# MCU_et_al.net
KiCad netlist of a schematic drawn in Altium Designer
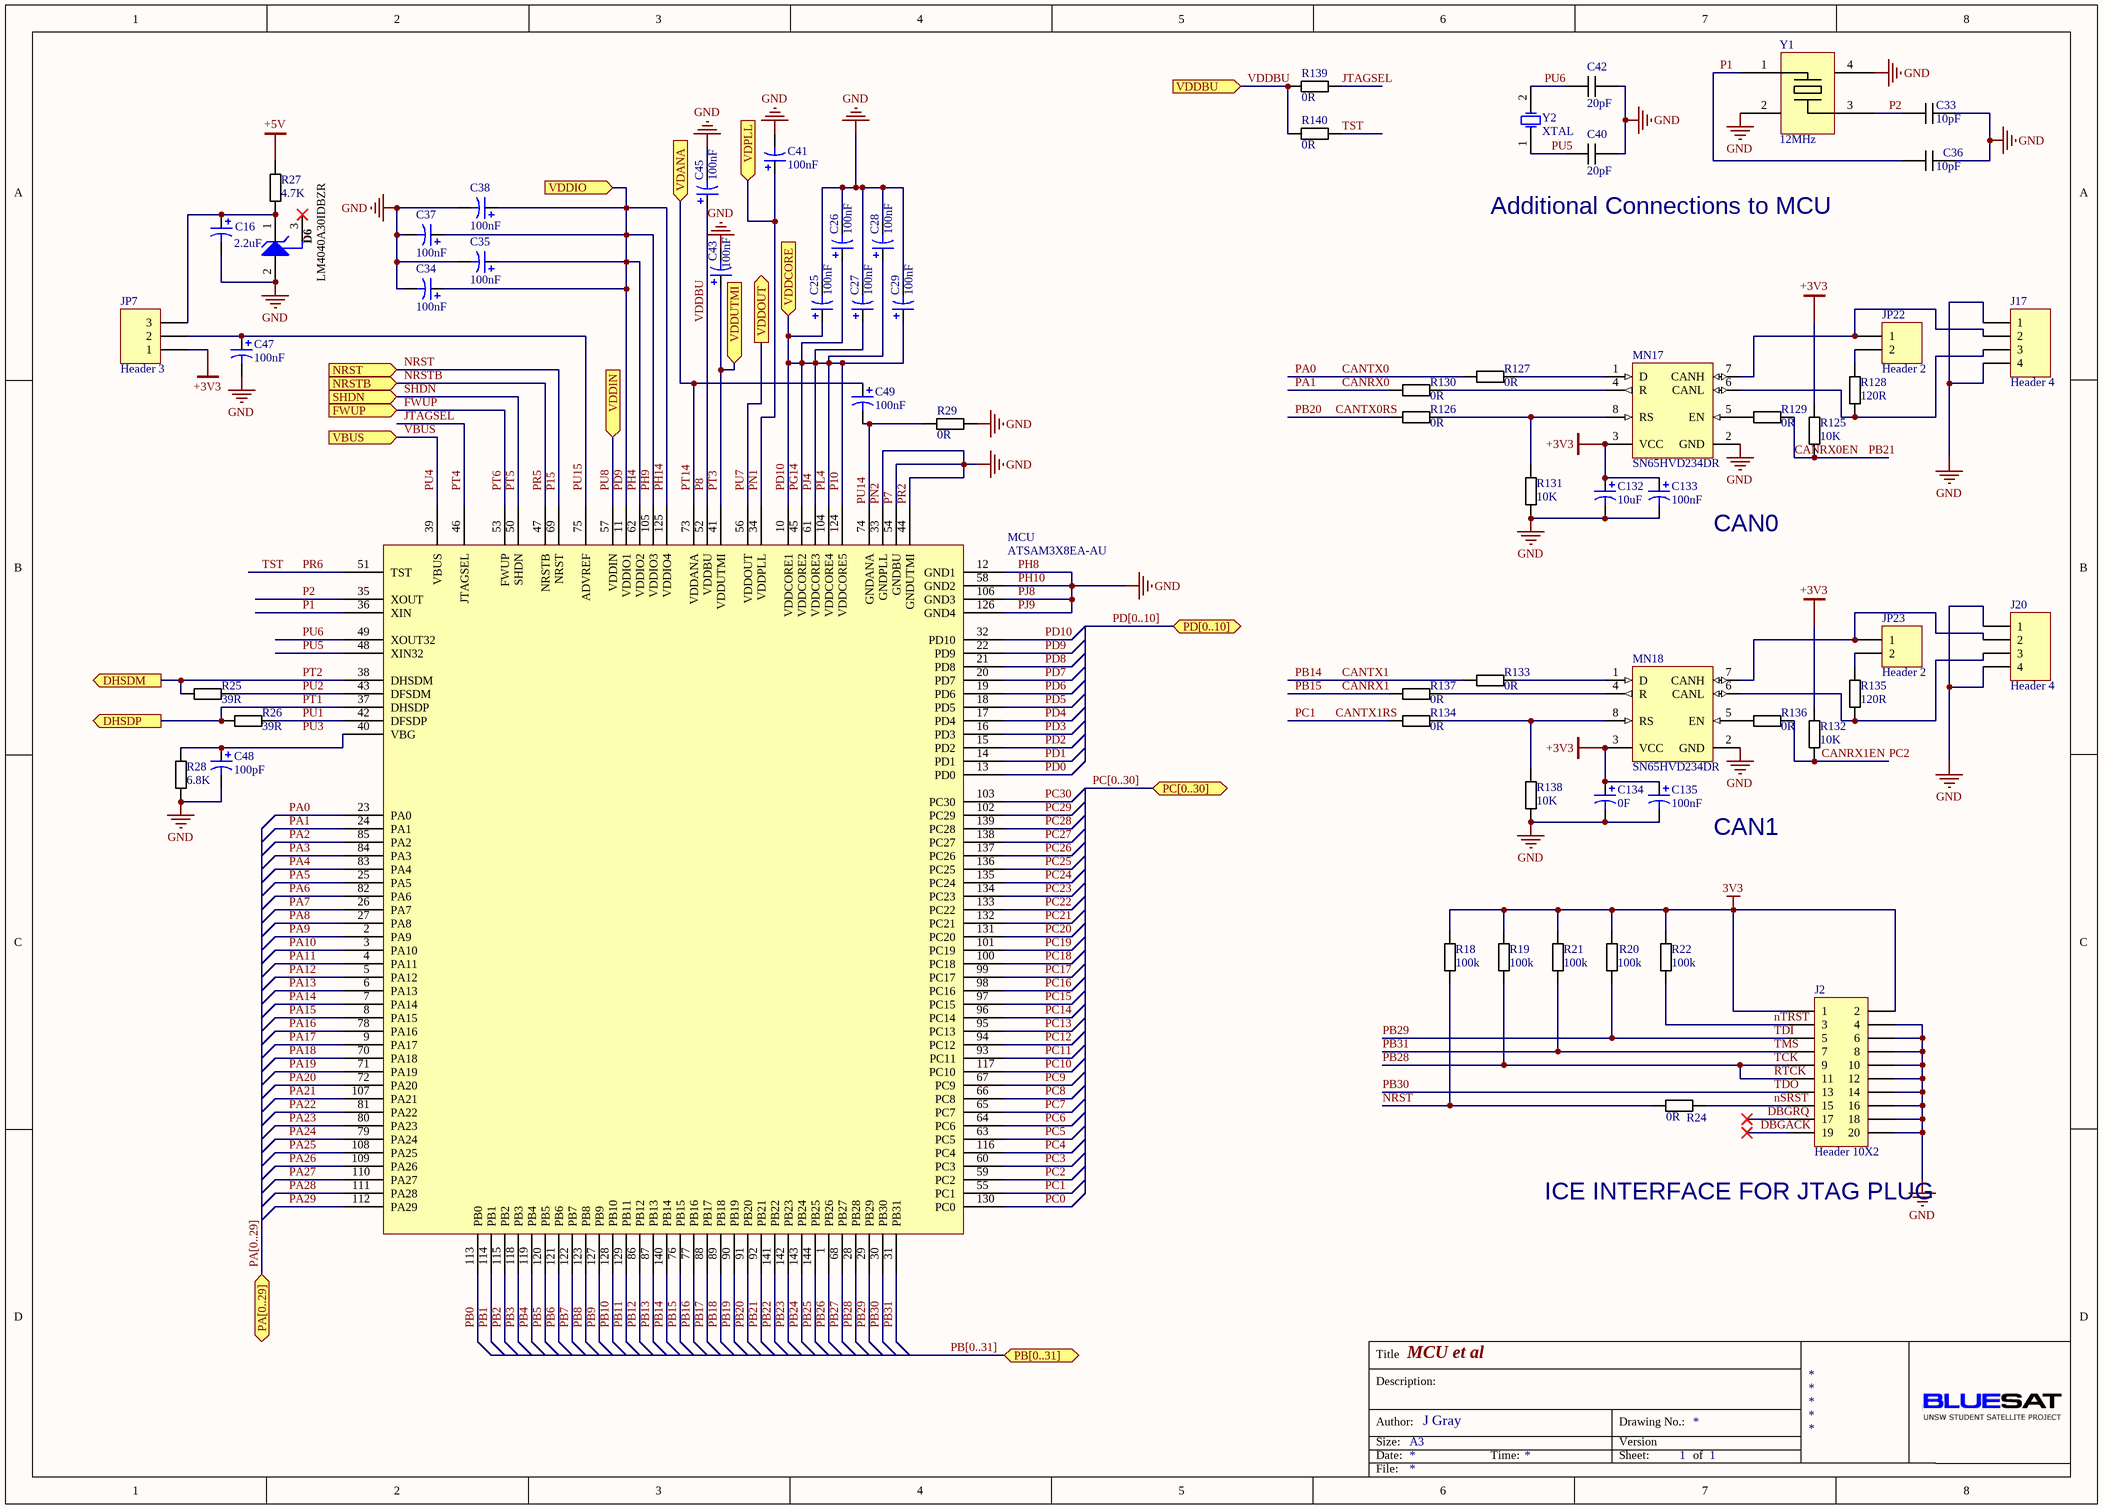
[diagram p0: MCU et al.SchDoc]

(export (version "E")
  (design (tool "Eeschema 10.0.6"))
  (components
    (comp (ref "C16")
      (value "2.2uF")
      (footprint "0805 Cap")
      (description "Polarized Capacitor (Surface Mount)")
      (fields (field (name "Comment") "Cap Pol3") (field (name "PUBLISHER") "Altium Limited"))
      (libsource (lib "Miscellaneous Devices") (part "Cap Pol3"))
    )
    (comp (ref "C25")
      (value "100nF")
      (footprint "0805 Cap")
      (description "Polarized Capacitor (Surface Mount)")
      (fields (field (name "Comment") "Cap Pol3") (field (name "PUBLISHER") "Altium Limited"))
      (libsource (lib "Miscellaneous Devices") (part "Cap Pol3"))
    )
    (comp (ref "C26")
      (value "100nF")
      (footprint "0805 Cap")
      (description "Polarized Capacitor (Surface Mount)")
      (fields (field (name "Comment") "Cap Pol3") (field (name "PUBLISHER") "Altium Limited"))
      (libsource (lib "Miscellaneous Devices") (part "Cap Pol3"))
    )
    (comp (ref "C27")
      (value "100nF")
      (footprint "0805 Cap")
      (description "Polarized Capacitor (Surface Mount)")
      (fields (field (name "Comment") "Cap Pol3") (field (name "PUBLISHER") "Altium Limited"))
      (libsource (lib "Miscellaneous Devices") (part "Cap Pol3"))
    )
    (comp (ref "C28")
      (value "100nF")
      (footprint "0805 Cap")
      (description "Polarized Capacitor (Surface Mount)")
      (fields (field (name "Comment") "Cap Pol3") (field (name "PUBLISHER") "Altium Limited"))
      (libsource (lib "Miscellaneous Devices") (part "Cap Pol3"))
    )
    (comp (ref "C29")
      (value "100nF")
      (footprint "0805 Cap")
      (description "Polarized Capacitor (Surface Mount)")
      (fields (field (name "Comment") "Cap Pol3") (field (name "PUBLISHER") "Altium Limited"))
      (libsource (lib "Miscellaneous Devices") (part "Cap Pol3"))
    )
    (comp (ref "C33")
      (value "10pF")
      (footprint "0805 Cap")
      (description "0805 MLCC - X7R, 10%")
      (fields (field (name "Comment") "0805 Cap"))
      (libsource (lib "Schlib1") (part "0805 MLCC - X7R, 10%"))
    )
    (comp (ref "C34")
      (value "100nF")
      (footprint "0805 Cap")
      (description "Polarized Capacitor (Surface Mount)")
      (fields (field (name "Comment") "Cap Pol3") (field (name "PUBLISHER") "Altium Limited"))
      (libsource (lib "Miscellaneous Devices") (part "Cap Pol3"))
    )
    (comp (ref "C35")
      (value "100nF")
      (footprint "0805 Cap")
      (description "Polarized Capacitor (Surface Mount)")
      (fields (field (name "Comment") "Cap Pol3") (field (name "PUBLISHER") "Altium Limited"))
      (libsource (lib "Miscellaneous Devices") (part "Cap Pol3"))
    )
    (comp (ref "C36")
      (value "10pF")
      (footprint "0805 Cap")
      (description "0805 MLCC - X7R, 10%")
      (fields (field (name "Comment") "0805 Cap"))
      (libsource (lib "Schlib1") (part "0805 MLCC - X7R, 10%"))
    )
    (comp (ref "C37")
      (value "100nF")
      (footprint "0805 Cap")
      (description "Polarized Capacitor (Surface Mount)")
      (fields (field (name "Comment") "Cap Pol3") (field (name "PUBLISHER") "Altium Limited"))
      (libsource (lib "Miscellaneous Devices") (part "Cap Pol3"))
    )
    (comp (ref "C38")
      (value "100nF")
      (footprint "0805 Cap")
      (description "Polarized Capacitor (Surface Mount)")
      (fields (field (name "Comment") "Cap Pol3") (field (name "PUBLISHER") "Altium Limited"))
      (libsource (lib "Miscellaneous Devices") (part "Cap Pol3"))
    )
    (comp (ref "C40")
      (value "20pF")
      (footprint "0805 Cap")
      (description "0805 MLCC - X7R, 10%")
      (fields (field (name "Comment") "0805 Cap"))
      (libsource (lib "Schlib1") (part "0805 MLCC - X7R, 10%"))
    )
    (comp (ref "C41")
      (value "100nF")
      (footprint "0805 Cap")
      (description "Polarized Capacitor (Surface Mount)")
      (fields (field (name "Comment") "Cap Pol3") (field (name "PUBLISHER") "Altium Limited"))
      (libsource (lib "Miscellaneous Devices") (part "Cap Pol3"))
    )
    (comp (ref "C42")
      (value "20pF")
      (footprint "0805 Cap")
      (description "0805 MLCC - X7R, 10%")
      (fields (field (name "Comment") "0805 Cap"))
      (libsource (lib "Schlib1") (part "0805 MLCC - X7R, 10%"))
    )
    (comp (ref "C43")
      (value "100nF")
      (footprint "0805 Cap")
      (description "Polarized Capacitor (Surface Mount)")
      (fields (field (name "Comment") "Cap Pol3") (field (name "PUBLISHER") "Altium Limited"))
      (libsource (lib "Miscellaneous Devices") (part "Cap Pol3"))
    )
    (comp (ref "C45")
      (value "100nF")
      (footprint "0805 Cap")
      (description "Polarized Capacitor (Surface Mount)")
      (fields (field (name "Comment") "Cap Pol3") (field (name "PUBLISHER") "Altium Limited"))
      (libsource (lib "Miscellaneous Devices") (part "Cap Pol3"))
    )
    (comp (ref "C47")
      (value "100nF")
      (footprint "0805 Cap")
      (description "Polarized Capacitor (Surface Mount)")
      (fields (field (name "Comment") "Cap Pol3") (field (name "PUBLISHER") "Altium Limited"))
      (libsource (lib "Miscellaneous Devices") (part "Cap Pol3"))
    )
    (comp (ref "C48")
      (value "100pF")
      (footprint "0805 Cap")
      (description "Polarized Capacitor (Surface Mount)")
      (fields (field (name "Comment") "Cap Pol3") (field (name "PUBLISHER") "Altium Limited"))
      (libsource (lib "Miscellaneous Devices") (part "Cap Pol3"))
    )
    (comp (ref "C49")
      (value "100nF")
      (footprint "0805 Cap")
      (description "Polarized Capacitor (Surface Mount)")
      (fields (field (name "Comment") "Cap Pol3") (field (name "PUBLISHER") "Altium Limited"))
      (libsource (lib "Miscellaneous Devices") (part "Cap Pol3"))
    )
    (comp (ref "C132")
      (value "10uF")
      (footprint "0805 Cap")
      (description "Polarized Capacitor (Surface Mount)")
      (fields (field (name "Comment") "Cap Pol3") (field (name "PUBLISHER") "Altium Limited"))
      (libsource (lib "Miscellaneous Devices") (part "Cap Pol3"))
    )
    (comp (ref "C133")
      (value "100nF")
      (footprint "0805 Cap")
      (description "Polarized Capacitor (Surface Mount)")
      (fields (field (name "Comment") "Cap Pol3") (field (name "PUBLISHER") "Altium Limited"))
      (libsource (lib "Miscellaneous Devices") (part "Cap Pol3"))
    )
    (comp (ref "C134")
      (value "0F")
      (footprint "0805 Cap")
      (description "Polarized Capacitor (Surface Mount)")
      (fields (field (name "Comment") "Cap Pol3") (field (name "PUBLISHER") "Altium Limited"))
      (libsource (lib "Miscellaneous Devices") (part "Cap Pol3"))
    )
    (comp (ref "C135")
      (value "100nF")
      (footprint "0805 Cap")
      (description "Polarized Capacitor (Surface Mount)")
      (fields (field (name "Comment") "Cap Pol3") (field (name "PUBLISHER") "Altium Limited"))
      (libsource (lib "Miscellaneous Devices") (part "Cap Pol3"))
    )
    (comp (ref "D6")
      (value "LM4040A30IDBZR")
      (footprint "TI-DBZ3_N")
      (fields (field (name "MANUFACTURER") "Texas Instruments"))
      (libsource (lib "TI Power Management Shunt Voltage Reference") (part "LM4040A30IDBZR"))
    )
    (comp (ref "J2")
      (value "Header 10X2")
      (footprint "HDR2X10 (JTAG)")
      (description "Header, 10-Pin, Dual row")
      (fields (field (name "PUBLISHER") "Altium Limited"))
      (libsource (lib "Miscellaneous Connectors") (part "Header 10X2"))
    )
    (comp (ref "J17")
      (value "Header 4")
      (footprint "HDR1X4")
      (description "Header, 4-Pin")
      (fields (field (name "PUBLISHER") "Altium Limited"))
      (libsource (lib "Miscellaneous Connectors") (part "Header 4"))
    )
    (comp (ref "J20")
      (value "Header 4")
      (footprint "HDR1X4")
      (description "Header, 4-Pin")
      (fields (field (name "PUBLISHER") "Altium Limited"))
      (libsource (lib "Miscellaneous Connectors") (part "Header 4"))
    )
    (comp (ref "JP7")
      (value "Header 3")
      (footprint "HDR1X3")
      (description "Header, 3-Pin, fix symbol later")
      (fields (field (name "PUBLISHER") "Altium Limited"))
      (libsource (lib "Miscellaneous Connectors") (part "Header 3"))
    )
    (comp (ref "JP22")
      (value "Header 2")
      (footprint "HDR1X2")
      (description "Header, 2-Pin")
      (fields (field (name "MANUFACTURER") "Molex"))
      (libsource (lib "Tray 1 Expansion Board Prototype") (part "Header 2"))
    )
    (comp (ref "JP23")
      (value "Header 2")
      (footprint "HDR1X2")
      (description "Header, 2-Pin")
      (fields (field (name "MANUFACTURER") "Molex"))
      (libsource (lib "Tray 1 Expansion Board Prototype") (part "Header 2"))
    )
    (comp (ref "MCU")
      (value "ATSAM3X8EA-AU")
      (footprint "LQFP144_M")
      (description "ATSAM3X8EA-AU ARM CORTEX M3 Microcontroller")
      (libsource (lib "Integrated_circuits") (part "ATSAM3X8E"))
    )
    (comp (ref "MN17")
      (value "SN65HVD234DR")
      (footprint "D8_L")
      (description "3.3V CAN Transceiver with Sleep Mode, 6 mA, -40 to Digi-Key Number 296-27991-1-ND")
      (fields (field (name "MANUFACTURER") "Texas Instruments"))
      (libsource (lib "Texas Instruments Interface CAN") (part "SN65HVD234DR"))
    )
    (comp (ref "MN18")
      (value "SN65HVD234DR")
      (footprint "D8_L")
      (description "Digi-Key Number 296-27991-1-ND")
      (fields (field (name "MANUFACTURER") "Texas Instruments"))
      (libsource (lib "Texas Instruments Interface CAN") (part "SN65HVD234DR"))
    )
    (comp (ref "R18")
      (value "100k")
      (footprint "0805 Resistor")
      (description "0805 Thick Film Resistor 1%")
      (fields (field (name "Comment") "0805 Resistor"))
      (libsource (lib "") (part "0805 Thick Film Resistor 1%_1"))
    )
    (comp (ref "R19")
      (value "100k")
      (footprint "0805 Resistor")
      (description "0805 Thick Film Resistor 1%")
      (fields (field (name "Comment") "0805 Resistor"))
      (libsource (lib "") (part "0805 Thick Film Resistor 1%_1"))
    )
    (comp (ref "R20")
      (value "100k")
      (footprint "0805 Resistor")
      (description "0805 Thick Film Resistor 1%")
      (fields (field (name "Comment") "0805 Resistor"))
      (libsource (lib "") (part "0805 Thick Film Resistor 1%_1"))
    )
    (comp (ref "R21")
      (value "100k")
      (footprint "0805 Resistor")
      (description "0805 Thick Film Resistor 1%")
      (fields (field (name "Comment") "0805 Resistor"))
      (libsource (lib "") (part "0805 Thick Film Resistor 1%_1"))
    )
    (comp (ref "R22")
      (value "100k")
      (footprint "0805 Resistor")
      (description "0805 Thick Film Resistor 1%")
      (fields (field (name "Comment") "0805 Resistor"))
      (libsource (lib "") (part "0805 Thick Film Resistor 1%_1"))
    )
    (comp (ref "R24")
      (value "0R")
      (footprint "0805 Resistor")
      (description "0805 Thick Film Resistor 1%")
      (fields (field (name "Comment") "0805 Resistor"))
      (libsource (lib "Schlib1") (part "0805 Thick Film Resistor 1%"))
    )
    (comp (ref "R25")
      (value "39R")
      (footprint "0805 Resistor")
      (description "0805 Thick Film Resistor 1%")
      (fields (field (name "Comment") "0805 Resistor"))
      (libsource (lib "Schlib1") (part "0805 Thick Film Resistor 1%"))
    )
    (comp (ref "R26")
      (value "39R")
      (footprint "0805 Resistor")
      (description "0805 Thick Film Resistor 1%")
      (fields (field (name "Comment") "0805 Resistor"))
      (libsource (lib "Schlib1") (part "0805 Thick Film Resistor 1%"))
    )
    (comp (ref "R27")
      (value "4.7K")
      (footprint "0805 Resistor")
      (description "0805 Thick Film Resistor 1%")
      (fields (field (name "Comment") "0805 Resistor"))
      (libsource (lib "") (part "0805 Thick Film Resistor 1%_1"))
    )
    (comp (ref "R28")
      (value "6.8K")
      (footprint "0805 Resistor")
      (description "0805 Thick Film Resistor 1%")
      (fields (field (name "Comment") "0805 Resistor"))
      (libsource (lib "") (part "0805 Thick Film Resistor 1%_1"))
    )
    (comp (ref "R29")
      (value "0R")
      (footprint "0805 Resistor")
      (description "0805 Thick Film Resistor 1%")
      (fields (field (name "Comment") "0805 Resistor"))
      (libsource (lib "") (part "0805 Thick Film Resistor 1%_3"))
    )
    (comp (ref "R125")
      (value "10K")
      (footprint "0805 Resistor")
      (description "0805 Thick Film Resistor 1%")
      (fields (field (name "Comment") "0805 Resistor"))
      (libsource (lib "") (part "0805 Thick Film Resistor 1%_1"))
    )
    (comp (ref "R126")
      (value "0R")
      (footprint "0805 Resistor")
      (description "0805 Thick Film Resistor 1%")
      (fields (field (name "Comment") "0805 Resistor"))
      (libsource (lib "Schlib1") (part "0805 Thick Film Resistor 1%"))
    )
    (comp (ref "R127")
      (value "0R")
      (footprint "0805 Resistor")
      (description "0805 Thick Film Resistor 1%")
      (fields (field (name "Comment") "0805 Resistor"))
      (libsource (lib "Schlib1") (part "0805 Thick Film Resistor 1%"))
    )
    (comp (ref "R128")
      (value "120R")
      (footprint "0805 Resistor")
      (description "0805 Thick Film Resistor 1%")
      (fields (field (name "Comment") "0805 Resistor"))
      (libsource (lib "") (part "0805 Thick Film Resistor 1%_2"))
    )
    (comp (ref "R129")
      (value "0R")
      (footprint "0805 Resistor")
      (description "0805 Thick Film Resistor 1%")
      (fields (field (name "Comment") "0805 Resistor"))
      (libsource (lib "Schlib1") (part "0805 Thick Film Resistor 1%"))
    )
    (comp (ref "R130")
      (value "0R")
      (footprint "0805 Resistor")
      (description "0805 Thick Film Resistor 1%")
      (fields (field (name "Comment") "0805 Resistor"))
      (libsource (lib "Schlib1") (part "0805 Thick Film Resistor 1%"))
    )
    (comp (ref "R131")
      (value "10K")
      (footprint "0805 Resistor")
      (description "0805 Thick Film Resistor 1%")
      (fields (field (name "Comment") "0805 Resistor"))
      (libsource (lib "") (part "0805 Thick Film Resistor 1%_1"))
    )
    (comp (ref "R132")
      (value "10K")
      (footprint "0805 Resistor")
      (description "0805 Thick Film Resistor 1%")
      (fields (field (name "Comment") "0805 Resistor"))
      (libsource (lib "") (part "0805 Thick Film Resistor 1%_1"))
    )
    (comp (ref "R133")
      (value "0R")
      (footprint "0805 Resistor")
      (description "0805 Thick Film Resistor 1%")
      (fields (field (name "Comment") "0805 Resistor"))
      (libsource (lib "Schlib1") (part "0805 Thick Film Resistor 1%"))
    )
    (comp (ref "R134")
      (value "0R")
      (footprint "0805 Resistor")
      (description "0805 Thick Film Resistor 1%")
      (fields (field (name "Comment") "0805 Resistor"))
      (libsource (lib "Schlib1") (part "0805 Thick Film Resistor 1%"))
    )
    (comp (ref "R135")
      (value "120R")
      (footprint "0805 Resistor")
      (description "0805 Thick Film Resistor 1%")
      (fields (field (name "Comment") "0805 Resistor"))
      (libsource (lib "") (part "0805 Thick Film Resistor 1%_2"))
    )
    (comp (ref "R136")
      (value "0R")
      (footprint "0805 Resistor")
      (description "0805 Thick Film Resistor 1%")
      (fields (field (name "Comment") "0805 Resistor"))
      (libsource (lib "Schlib1") (part "0805 Thick Film Resistor 1%"))
    )
    (comp (ref "R137")
      (value "0R")
      (footprint "0805 Resistor")
      (description "0805 Thick Film Resistor 1%")
      (fields (field (name "Comment") "0805 Resistor"))
      (libsource (lib "Schlib1") (part "0805 Thick Film Resistor 1%"))
    )
    (comp (ref "R138")
      (value "10K")
      (footprint "0805 Resistor")
      (description "0805 Thick Film Resistor 1%")
      (fields (field (name "Comment") "0805 Resistor"))
      (libsource (lib "") (part "0805 Thick Film Resistor 1%_1"))
    )
    (comp (ref "R139")
      (value "0R")
      (footprint "0805 Resistor")
      (description "0805 Thick Film Resistor 1%")
      (fields (field (name "Comment") "0805 Resistor"))
      (libsource (lib "Schlib1") (part "0805 Thick Film Resistor 1%"))
    )
    (comp (ref "R140")
      (value "0R")
      (footprint "0805 Resistor")
      (description "0805 Thick Film Resistor 1%")
      (fields (field (name "Comment") "0805 Resistor"))
      (libsource (lib "Schlib1") (part "0805 Thick Film Resistor 1%"))
    )
    (comp (ref "Y1")
      (value "12MHz")
      (footprint "7V-12.000MAAE-T")
      (description "Digi-Key Part Number 887-1458-1-ND")
      (libsource (lib "Integrated_circuits") (part "4-Pin Oscillator"))
    )
    (comp (ref "Y2")
      (value "XTAL")
      (footprint "ABS07")
      (description "Digikey Number: 535-9544-1-ND")
      (fields (field (name "PUBLISHER") "Altium Limited"))
      (libsource (lib "Miscellaneous Devices") (part "XTAL"))
    )
  )
  (nets
    (net (code "1") (name "+3V3") (class "Default")
      (node (ref "C132") (pin "1") (pinfunction "1_1") (pintype "passive"))
      (node (ref "C133") (pin "1") (pinfunction "1_1") (pintype "passive"))
      (node (ref "C134") (pin "1") (pinfunction "1_1") (pintype "passive"))
      (node (ref "C135") (pin "1") (pinfunction "1_1") (pintype "passive"))
      (node (ref "JP7") (pin "1") (pinfunction "1_1") (pintype "passive"))
      (node (ref "MN17") (pin "3") (pinfunction "VCC_3") (pintype "power_in"))
      (node (ref "MN18") (pin "3") (pinfunction "VCC_3") (pintype "power_in"))
      (node (ref "R125") (pin "2") (pinfunction "2_2") (pintype "passive"))
      (node (ref "R132") (pin "2") (pinfunction "2_2") (pintype "passive"))
    )
    (net (code "2") (name "+5V") (class "Default")
      (node (ref "R27") (pin "2") (pinfunction "2_2") (pintype "passive"))
    )
    (net (code "3") (name "/DBGACK") (class "Default")
      (node (ref "J2") (pin "19") (pinfunction "19_19") (pintype "passive+no_connect"))
    )
    (net (code "4") (name "/DBGRQ") (class "Default")
      (node (ref "J2") (pin "17") (pinfunction "17_17") (pintype "passive+no_connect"))
    )
    (net (code "5") (name "/FWUP") (class "Default")
      (node (ref "MCU") (pin "53") (pinfunction "FWUP_53") (pintype "passive"))
    )
    (net (code "6") (name "/JTAGSEL") (class "Default")
      (node (ref "MCU") (pin "46") (pinfunction "JTAGSEL_46") (pintype "passive"))
      (node (ref "R139") (pin "2") (pinfunction "2_2") (pintype "passive"))
    )
    (net (code "7") (name "/NRST") (class "Default")
      (node (ref "MCU") (pin "69") (pinfunction "NRST_69") (pintype "passive"))
      (node (ref "R18") (pin "1") (pinfunction "1_1") (pintype "passive"))
      (node (ref "R24") (pin "1") (pinfunction "1_1") (pintype "passive"))
    )
    (net (code "8") (name "/NRSTB") (class "Default")
      (node (ref "MCU") (pin "47") (pinfunction "NRSTB_47") (pintype "passive"))
    )
    (net (code "9") (name "/P1") (class "Default")
      (node (ref "C36") (pin "1") (pinfunction "1_1") (pintype "passive"))
      (node (ref "MCU") (pin "36") (pinfunction "XIN_36") (pintype "passive"))
      (node (ref "Y1") (pin "1") (pinfunction "1_1") (pintype "passive"))
    )
    (net (code "10") (name "/P2") (class "Default")
      (node (ref "C33") (pin "1") (pinfunction "1_1") (pintype "passive"))
      (node (ref "MCU") (pin "35") (pinfunction "XOUT_35") (pintype "passive"))
      (node (ref "Y1") (pin "3") (pinfunction "3_3") (pintype "passive"))
    )
    (net (code "11") (name "/P8") (class "Default")
      (node (ref "C45") (pin "1") (pinfunction "1_1") (pintype "passive"))
      (node (ref "MCU") (pin "52") (pinfunction "VDDBU_52") (pintype "power_in"))
      (node (ref "R139") (pin "1") (pinfunction "1_1") (pintype "passive"))
      (node (ref "R140") (pin "1") (pinfunction "1_1") (pintype "passive"))
    )
    (net (code "12") (name "/PA0") (class "Default")
      (node (ref "MCU") (pin "23") (pinfunction "PA0_23") (pintype "passive"))
      (node (ref "R127") (pin "1") (pinfunction "1_1") (pintype "passive"))
    )
    (net (code "13") (name "/PA1") (class "Default")
      (node (ref "MCU") (pin "24") (pinfunction "PA1_24") (pintype "passive"))
      (node (ref "R130") (pin "1") (pinfunction "1_1") (pintype "passive"))
    )
    (net (code "14") (name "/PA2") (class "Default")
      (node (ref "MCU") (pin "85") (pinfunction "PA2_85") (pintype "passive"))
    )
    (net (code "15") (name "/PA3") (class "Default")
      (node (ref "MCU") (pin "84") (pinfunction "PA3_84") (pintype "passive"))
    )
    (net (code "16") (name "/PA4") (class "Default")
      (node (ref "MCU") (pin "83") (pinfunction "PA4_83") (pintype "passive"))
    )
    (net (code "17") (name "/PA5") (class "Default")
      (node (ref "MCU") (pin "25") (pinfunction "PA5_25") (pintype "passive"))
    )
    (net (code "18") (name "/PA6") (class "Default")
      (node (ref "MCU") (pin "82") (pinfunction "PA6_82") (pintype "passive"))
    )
    (net (code "19") (name "/PA7") (class "Default")
      (node (ref "MCU") (pin "26") (pinfunction "PA7_26") (pintype "passive"))
    )
    (net (code "20") (name "/PA8") (class "Default")
      (node (ref "MCU") (pin "27") (pinfunction "PA8_27") (pintype "passive"))
    )
    (net (code "21") (name "/PA9") (class "Default")
      (node (ref "MCU") (pin "2") (pinfunction "PA9_2") (pintype "passive"))
    )
    (net (code "22") (name "/PA10") (class "Default")
      (node (ref "MCU") (pin "3") (pinfunction "PA10_3") (pintype "passive"))
    )
    (net (code "23") (name "/PA11") (class "Default")
      (node (ref "MCU") (pin "4") (pinfunction "PA11_4") (pintype "passive"))
    )
    (net (code "24") (name "/PA12") (class "Default")
      (node (ref "MCU") (pin "5") (pinfunction "PA12_5") (pintype "passive"))
    )
    (net (code "25") (name "/PA13") (class "Default")
      (node (ref "MCU") (pin "6") (pinfunction "PA13_6") (pintype "passive"))
    )
    (net (code "26") (name "/PA14") (class "Default")
      (node (ref "MCU") (pin "7") (pinfunction "PA14_7") (pintype "passive"))
    )
    (net (code "27") (name "/PA15") (class "Default")
      (node (ref "MCU") (pin "8") (pinfunction "PA15_8") (pintype "passive"))
    )
    (net (code "28") (name "/PA16") (class "Default")
      (node (ref "MCU") (pin "78") (pinfunction "PA16_78") (pintype "passive"))
    )
    (net (code "29") (name "/PA17") (class "Default")
      (node (ref "MCU") (pin "9") (pinfunction "PA17_9") (pintype "passive"))
    )
    (net (code "30") (name "/PA18") (class "Default")
      (node (ref "MCU") (pin "70") (pinfunction "PA18_70") (pintype "passive"))
    )
    (net (code "31") (name "/PA19") (class "Default")
      (node (ref "MCU") (pin "71") (pinfunction "PA19_71") (pintype "passive"))
    )
    (net (code "32") (name "/PA20") (class "Default")
      (node (ref "MCU") (pin "72") (pinfunction "PA20_72") (pintype "passive"))
    )
    (net (code "33") (name "/PA21") (class "Default")
      (node (ref "MCU") (pin "107") (pinfunction "PA21_107") (pintype "passive"))
    )
    (net (code "34") (name "/PA22") (class "Default")
      (node (ref "MCU") (pin "81") (pinfunction "PA22_81") (pintype "passive"))
    )
    (net (code "35") (name "/PA23") (class "Default")
      (node (ref "MCU") (pin "80") (pinfunction "PA23_80") (pintype "passive"))
    )
    (net (code "36") (name "/PA24") (class "Default")
      (node (ref "MCU") (pin "79") (pinfunction "PA24_79") (pintype "passive"))
    )
    (net (code "37") (name "/PA25") (class "Default")
      (node (ref "MCU") (pin "108") (pinfunction "PA25_108") (pintype "passive"))
    )
    (net (code "38") (name "/PA26") (class "Default")
      (node (ref "MCU") (pin "109") (pinfunction "PA26_109") (pintype "passive"))
    )
    (net (code "39") (name "/PA27") (class "Default")
      (node (ref "MCU") (pin "110") (pinfunction "PA27_110") (pintype "passive"))
    )
    (net (code "40") (name "/PA28") (class "Default")
      (node (ref "MCU") (pin "111") (pinfunction "PA28_111") (pintype "passive"))
    )
    (net (code "41") (name "/PA29") (class "Default")
      (node (ref "MCU") (pin "112") (pinfunction "PA29_112") (pintype "passive"))
    )
    (net (code "43") (name "/PB0") (class "Default")
      (node (ref "MCU") (pin "113") (pinfunction "PB0_113") (pintype "passive"))
    )
    (net (code "44") (name "/PB1") (class "Default")
      (node (ref "MCU") (pin "114") (pinfunction "PB1_114") (pintype "passive"))
    )
    (net (code "45") (name "/PB2") (class "Default")
      (node (ref "MCU") (pin "115") (pinfunction "PB2_115") (pintype "passive"))
    )
    (net (code "46") (name "/PB3") (class "Default")
      (node (ref "MCU") (pin "118") (pinfunction "PB3_118") (pintype "passive"))
    )
    (net (code "47") (name "/PB4") (class "Default")
      (node (ref "MCU") (pin "119") (pinfunction "PB4_119") (pintype "passive"))
    )
    (net (code "48") (name "/PB5") (class "Default")
      (node (ref "MCU") (pin "120") (pinfunction "PB5_120") (pintype "passive"))
    )
    (net (code "49") (name "/PB6") (class "Default")
      (node (ref "MCU") (pin "121") (pinfunction "PB6_121") (pintype "passive"))
    )
    (net (code "50") (name "/PB7") (class "Default")
      (node (ref "MCU") (pin "122") (pinfunction "PB7_122") (pintype "passive"))
    )
    (net (code "51") (name "/PB8") (class "Default")
      (node (ref "MCU") (pin "123") (pinfunction "PB8_123") (pintype "passive"))
    )
    (net (code "52") (name "/PB9") (class "Default")
      (node (ref "MCU") (pin "127") (pinfunction "PB9_127") (pintype "passive"))
    )
    (net (code "53") (name "/PB10") (class "Default")
      (node (ref "MCU") (pin "128") (pinfunction "PB10_128") (pintype "passive"))
    )
    (net (code "54") (name "/PB11") (class "Default")
      (node (ref "MCU") (pin "129") (pinfunction "PB11_129") (pintype "passive"))
    )
    (net (code "55") (name "/PB12") (class "Default")
      (node (ref "MCU") (pin "86") (pinfunction "PB12_86") (pintype "passive"))
    )
    (net (code "56") (name "/PB13") (class "Default")
      (node (ref "MCU") (pin "87") (pinfunction "PB13_87") (pintype "passive"))
    )
    (net (code "57") (name "/PB14") (class "Default")
      (node (ref "MCU") (pin "140") (pinfunction "PB14_140") (pintype "passive"))
      (node (ref "R133") (pin "1") (pinfunction "1_1") (pintype "passive"))
    )
    (net (code "58") (name "/PB15") (class "Default")
      (node (ref "MCU") (pin "76") (pinfunction "PB15_76") (pintype "passive"))
      (node (ref "R137") (pin "1") (pinfunction "1_1") (pintype "passive"))
    )
    (net (code "59") (name "/PB16") (class "Default")
      (node (ref "MCU") (pin "77") (pinfunction "PB16_77") (pintype "passive"))
    )
    (net (code "60") (name "/PB17") (class "Default")
      (node (ref "MCU") (pin "88") (pinfunction "PB17_88") (pintype "passive"))
    )
    (net (code "61") (name "/PB18") (class "Default")
      (node (ref "MCU") (pin "89") (pinfunction "PB18_89") (pintype "passive"))
    )
    (net (code "62") (name "/PB19") (class "Default")
      (node (ref "MCU") (pin "90") (pinfunction "PB19_90") (pintype "passive"))
    )
    (net (code "63") (name "/PB20") (class "Default")
      (node (ref "MCU") (pin "91") (pinfunction "PB20_91") (pintype "passive"))
      (node (ref "R126") (pin "1") (pinfunction "1_1") (pintype "passive"))
    )
    (net (code "64") (name "/PB21") (class "Default")
      (node (ref "MCU") (pin "92") (pinfunction "PB21_92") (pintype "passive"))
      (node (ref "R125") (pin "1") (pinfunction "1_1") (pintype "passive"))
      (node (ref "R129") (pin "2") (pinfunction "2_2") (pintype "passive"))
    )
    (net (code "65") (name "/PB22") (class "Default")
      (node (ref "MCU") (pin "141") (pinfunction "PB22_141") (pintype "passive"))
    )
    (net (code "66") (name "/PB23") (class "Default")
      (node (ref "MCU") (pin "142") (pinfunction "PB23_142") (pintype "passive"))
    )
    (net (code "67") (name "/PB24") (class "Default")
      (node (ref "MCU") (pin "143") (pinfunction "PB24_143") (pintype "passive"))
    )
    (net (code "68") (name "/PB25") (class "Default")
      (node (ref "MCU") (pin "144") (pinfunction "PB25_144") (pintype "passive"))
    )
    (net (code "69") (name "/PB26") (class "Default")
      (node (ref "MCU") (pin "1") (pinfunction "PB26_1") (pintype "passive"))
    )
    (net (code "70") (name "/PB27") (class "Default")
      (node (ref "MCU") (pin "68") (pinfunction "PB27_68") (pintype "passive"))
    )
    (net (code "71") (name "/PB28") (class "Default")
      (node (ref "J2") (pin "11") (pinfunction "11_11") (pintype "passive"))
      (node (ref "J2") (pin "9") (pinfunction "9_9") (pintype "passive"))
      (node (ref "MCU") (pin "28") (pinfunction "PB28_28") (pintype "passive"))
      (node (ref "R19") (pin "1") (pinfunction "1_1") (pintype "passive"))
    )
    (net (code "72") (name "/PB29") (class "Default")
      (node (ref "J2") (pin "5") (pinfunction "5_5") (pintype "passive"))
      (node (ref "MCU") (pin "29") (pinfunction "PB29_29") (pintype "passive"))
      (node (ref "R20") (pin "1") (pinfunction "1_1") (pintype "passive"))
    )
    (net (code "73") (name "/PB30") (class "Default")
      (node (ref "J2") (pin "13") (pinfunction "13_13") (pintype "passive"))
      (node (ref "MCU") (pin "30") (pinfunction "PB30_30") (pintype "passive"))
    )
    (net (code "74") (name "/PB31") (class "Default")
      (node (ref "J2") (pin "7") (pinfunction "7_7") (pintype "passive"))
      (node (ref "MCU") (pin "31") (pinfunction "PB31_31") (pintype "passive"))
      (node (ref "R21") (pin "1") (pinfunction "1_1") (pintype "passive"))
    )
    (net (code "76") (name "/PC0") (class "Default")
      (node (ref "MCU") (pin "130") (pinfunction "PC0_130") (pintype "passive"))
    )
    (net (code "77") (name "/PC1") (class "Default")
      (node (ref "MCU") (pin "55") (pinfunction "PC1_55") (pintype "passive"))
      (node (ref "R134") (pin "1") (pinfunction "1_1") (pintype "passive"))
    )
    (net (code "78") (name "/PC2") (class "Default")
      (node (ref "MCU") (pin "59") (pinfunction "PC2_59") (pintype "passive"))
      (node (ref "R132") (pin "1") (pinfunction "1_1") (pintype "passive"))
      (node (ref "R136") (pin "2") (pinfunction "2_2") (pintype "passive"))
    )
    (net (code "79") (name "/PC3") (class "Default")
      (node (ref "MCU") (pin "60") (pinfunction "PC3_60") (pintype "passive"))
    )
    (net (code "80") (name "/PC4") (class "Default")
      (node (ref "MCU") (pin "116") (pinfunction "PC4_116") (pintype "passive"))
    )
    (net (code "81") (name "/PC5") (class "Default")
      (node (ref "MCU") (pin "63") (pinfunction "PC5_63") (pintype "passive"))
    )
    (net (code "82") (name "/PC6") (class "Default")
      (node (ref "MCU") (pin "64") (pinfunction "PC6_64") (pintype "passive"))
    )
    (net (code "83") (name "/PC7") (class "Default")
      (node (ref "MCU") (pin "65") (pinfunction "PC7_65") (pintype "passive"))
    )
    (net (code "84") (name "/PC8") (class "Default")
      (node (ref "MCU") (pin "66") (pinfunction "PC8_66") (pintype "passive"))
    )
    (net (code "85") (name "/PC9") (class "Default")
      (node (ref "MCU") (pin "67") (pinfunction "PC9_67") (pintype "passive"))
    )
    (net (code "86") (name "/PC10") (class "Default")
      (node (ref "MCU") (pin "117") (pinfunction "PC10_117") (pintype "passive"))
    )
    (net (code "87") (name "/PC11") (class "Default")
      (node (ref "MCU") (pin "93") (pinfunction "PC11_93") (pintype "passive"))
    )
    (net (code "88") (name "/PC12") (class "Default")
      (node (ref "MCU") (pin "94") (pinfunction "PC12_94") (pintype "passive"))
    )
    (net (code "89") (name "/PC13") (class "Default")
      (node (ref "MCU") (pin "95") (pinfunction "PC13_95") (pintype "passive"))
    )
    (net (code "90") (name "/PC14") (class "Default")
      (node (ref "MCU") (pin "96") (pinfunction "PC14_96") (pintype "passive"))
    )
    (net (code "91") (name "/PC15") (class "Default")
      (node (ref "MCU") (pin "97") (pinfunction "PC15_97") (pintype "passive"))
    )
    (net (code "92") (name "/PC16") (class "Default")
      (node (ref "MCU") (pin "98") (pinfunction "PC16_98") (pintype "passive"))
    )
    (net (code "93") (name "/PC17") (class "Default")
      (node (ref "MCU") (pin "99") (pinfunction "PC17_99") (pintype "passive"))
    )
    (net (code "94") (name "/PC18") (class "Default")
      (node (ref "MCU") (pin "100") (pinfunction "PC18_100") (pintype "passive"))
    )
    (net (code "95") (name "/PC19") (class "Default")
      (node (ref "MCU") (pin "101") (pinfunction "PC19_101") (pintype "passive"))
    )
    (net (code "96") (name "/PC20") (class "Default")
      (node (ref "MCU") (pin "131") (pinfunction "PC20_131") (pintype "passive"))
    )
    (net (code "97") (name "/PC21") (class "Default")
      (node (ref "MCU") (pin "132") (pinfunction "PC21_132") (pintype "passive"))
    )
    (net (code "98") (name "/PC22") (class "Default")
      (node (ref "MCU") (pin "133") (pinfunction "PC22_133") (pintype "passive"))
    )
    (net (code "99") (name "/PC23") (class "Default")
      (node (ref "MCU") (pin "134") (pinfunction "PC23_134") (pintype "passive"))
    )
    (net (code "100") (name "/PC24") (class "Default")
      (node (ref "MCU") (pin "135") (pinfunction "PC24_135") (pintype "passive"))
    )
    (net (code "101") (name "/PC25") (class "Default")
      (node (ref "MCU") (pin "136") (pinfunction "PC25_136") (pintype "passive"))
    )
    (net (code "102") (name "/PC26") (class "Default")
      (node (ref "MCU") (pin "137") (pinfunction "PC26_137") (pintype "passive"))
    )
    (net (code "103") (name "/PC27") (class "Default")
      (node (ref "MCU") (pin "138") (pinfunction "PC27_138") (pintype "passive"))
    )
    (net (code "104") (name "/PC28") (class "Default")
      (node (ref "MCU") (pin "139") (pinfunction "PC28_139") (pintype "passive"))
    )
    (net (code "105") (name "/PC29") (class "Default")
      (node (ref "MCU") (pin "102") (pinfunction "PC29_102") (pintype "passive"))
    )
    (net (code "106") (name "/PC30") (class "Default")
      (node (ref "MCU") (pin "103") (pinfunction "PC30_103") (pintype "passive"))
    )
    (net (code "108") (name "/PD0") (class "Default")
      (node (ref "MCU") (pin "13") (pinfunction "PD0_13") (pintype "passive"))
    )
    (net (code "109") (name "/PD1") (class "Default")
      (node (ref "MCU") (pin "14") (pinfunction "PD1_14") (pintype "passive"))
    )
    (net (code "110") (name "/PD2") (class "Default")
      (node (ref "MCU") (pin "15") (pinfunction "PD2_15") (pintype "passive"))
    )
    (net (code "111") (name "/PD3") (class "Default")
      (node (ref "MCU") (pin "16") (pinfunction "PD3_16") (pintype "passive"))
    )
    (net (code "112") (name "/PD4") (class "Default")
      (node (ref "MCU") (pin "17") (pinfunction "PD4_17") (pintype "passive"))
    )
    (net (code "113") (name "/PD5") (class "Default")
      (node (ref "MCU") (pin "18") (pinfunction "PD5_18") (pintype "passive"))
    )
    (net (code "114") (name "/PD6") (class "Default")
      (node (ref "MCU") (pin "19") (pinfunction "PD6_19") (pintype "passive"))
    )
    (net (code "115") (name "/PD7") (class "Default")
      (node (ref "MCU") (pin "20") (pinfunction "PD7_20") (pintype "passive"))
    )
    (net (code "116") (name "/PD8") (class "Default")
      (node (ref "MCU") (pin "21") (pinfunction "PD8_21") (pintype "passive"))
    )
    (net (code "117") (name "/PD9") (class "Default")
      (node (ref "C34") (pin "1") (pinfunction "1_1") (pintype "passive"))
      (node (ref "C35") (pin "1") (pinfunction "1_1") (pintype "passive"))
      (node (ref "C37") (pin "1") (pinfunction "1_1") (pintype "passive"))
      (node (ref "C38") (pin "1") (pinfunction "1_1") (pintype "passive"))
      (node (ref "MCU") (pin "105") (pinfunction "VDDIO3_105") (pintype "power_in"))
      (node (ref "MCU") (pin "11") (pinfunction "VDDIO1_11") (pintype "power_in"))
      (node (ref "MCU") (pin "125") (pinfunction "VDDIO4_125") (pintype "power_in"))
      (node (ref "MCU") (pin "22") (pinfunction "PD9_22") (pintype "passive"))
      (node (ref "MCU") (pin "62") (pinfunction "VDDIO2_62") (pintype "power_in"))
    )
    (net (code "118") (name "/PD10") (class "Default")
      (node (ref "C25") (pin "1") (pinfunction "1_1") (pintype "passive"))
      (node (ref "C26") (pin "1") (pinfunction "1_1") (pintype "passive"))
      (node (ref "C27") (pin "1") (pinfunction "1_1") (pintype "passive"))
      (node (ref "C28") (pin "1") (pinfunction "1_1") (pintype "passive"))
      (node (ref "C29") (pin "1") (pinfunction "1_1") (pintype "passive"))
      (node (ref "MCU") (pin "10") (pinfunction "VDDCORE1_10") (pintype "power_in"))
      (node (ref "MCU") (pin "104") (pinfunction "VDDCORE4_104") (pintype "power_in"))
      (node (ref "MCU") (pin "124") (pinfunction "VDDCORE5_124") (pintype "power_in"))
      (node (ref "MCU") (pin "32") (pinfunction "PD10_32") (pintype "passive"))
      (node (ref "MCU") (pin "45") (pinfunction "VDDCORE2_45") (pintype "power_in"))
      (node (ref "MCU") (pin "61") (pinfunction "VDDCORE3_61") (pintype "power_in"))
    )
    (net (code "120") (name "/PN1") (class "Default")
      (node (ref "C41") (pin "1") (pinfunction "1_1") (pintype "passive"))
      (node (ref "MCU") (pin "34") (pinfunction "VDDPLL_34") (pintype "power_in"))
    )
    (net (code "121") (name "/PR6") (class "Default")
      (node (ref "MCU") (pin "51") (pinfunction "TST_51") (pintype "passive"))
      (node (ref "R140") (pin "2") (pinfunction "2_2") (pintype "passive"))
    )
    (net (code "122") (name "/PT1") (class "Default")
      (node (ref "MCU") (pin "37") (pinfunction "DHSDP_37") (pintype "passive"))
      (node (ref "R26") (pin "1") (pinfunction "1_1") (pintype "passive"))
    )
    (net (code "123") (name "/PT2") (class "Default")
      (node (ref "MCU") (pin "38") (pinfunction "DHSDM_38") (pintype "passive"))
      (node (ref "R25") (pin "1") (pinfunction "1_1") (pintype "passive"))
    )
    (net (code "124") (name "/PT3") (class "Default")
      (node (ref "C43") (pin "1") (pinfunction "1_1") (pintype "passive"))
      (node (ref "MCU") (pin "41") (pinfunction "VDDUTMI_41") (pintype "power_in"))
    )
    (net (code "125") (name "/PT5") (class "Default")
      (node (ref "MCU") (pin "50") (pinfunction "SHDN_50") (pintype "passive"))
    )
    (net (code "126") (name "/PT14") (class "Default")
      (node (ref "C49") (pin "1") (pinfunction "1_1") (pintype "passive"))
      (node (ref "MCU") (pin "73") (pinfunction "VDDANA_73") (pintype "power_in"))
    )
    (net (code "127") (name "/PU1") (class "Default")
      (node (ref "MCU") (pin "42") (pinfunction "DFSDP_42") (pintype "passive"))
      (node (ref "R26") (pin "2") (pinfunction "2_2") (pintype "passive"))
    )
    (net (code "128") (name "/PU2") (class "Default")
      (node (ref "MCU") (pin "43") (pinfunction "DFSDM_43") (pintype "passive"))
      (node (ref "R25") (pin "2") (pinfunction "2_2") (pintype "passive"))
    )
    (net (code "130") (name "/PU4") (class "Default")
      (node (ref "MCU") (pin "39") (pinfunction "VBUS_39") (pintype "power_in"))
    )
    (net (code "131") (name "/PU5") (class "Default")
      (node (ref "C40") (pin "1") (pinfunction "1_1") (pintype "passive"))
      (node (ref "MCU") (pin "48") (pinfunction "XIN32_48") (pintype "passive"))
      (node (ref "Y2") (pin "1") (pinfunction "OSC1_1") (pintype "passive"))
    )
    (net (code "132") (name "/PU6") (class "Default")
      (node (ref "C42") (pin "1") (pinfunction "1_1") (pintype "passive"))
      (node (ref "MCU") (pin "49") (pinfunction "XOUT32_49") (pintype "passive"))
      (node (ref "Y2") (pin "2") (pinfunction "OSC2_2") (pintype "passive"))
    )
    (net (code "133") (name "/PU7") (class "Default")
      (node (ref "MCU") (pin "56") (pinfunction "VDDOUT_56") (pintype "power_in"))
    )
    (net (code "134") (name "/PU8") (class "Default")
      (node (ref "MCU") (pin "57") (pinfunction "VDDIN_57") (pintype "power_in"))
    )
    (net (code "135") (name "/PU14") (class "Default")
      (node (ref "C49") (pin "2") (pinfunction "2_2") (pintype "passive"))
      (node (ref "MCU") (pin "74") (pinfunction "GNDANA_74") (pintype "power_in"))
      (node (ref "R29") (pin "2") (pinfunction "2_2") (pintype "passive"))
    )
    (net (code "136") (name "/PU15") (class "Default")
      (node (ref "C47") (pin "1") (pinfunction "1_1") (pintype "passive"))
      (node (ref "JP7") (pin "2") (pinfunction "2_2") (pintype "passive"))
      (node (ref "MCU") (pin "75") (pinfunction "ADVREF_75") (pintype "passive"))
    )
    (net (code "137") (name "/nSRST") (class "Default")
      (node (ref "J2") (pin "15") (pinfunction "15_15") (pintype "passive"))
      (node (ref "R24") (pin "2") (pinfunction "2_2") (pintype "passive"))
    )
    (net (code "138") (name "/nTRST") (class "Default")
      (node (ref "J2") (pin "3") (pinfunction "3_3") (pintype "passive"))
      (node (ref "R22") (pin "1") (pinfunction "1_1") (pintype "passive"))
    )
    (net (code "139") (name "3V3") (class "Default")
      (node (ref "J2") (pin "1") (pinfunction "1_1") (pintype "passive"))
      (node (ref "J2") (pin "2") (pinfunction "2_2") (pintype "passive"))
      (node (ref "R18") (pin "2") (pinfunction "2_2") (pintype "passive"))
      (node (ref "R19") (pin "2") (pinfunction "2_2") (pintype "passive"))
      (node (ref "R20") (pin "2") (pinfunction "2_2") (pintype "passive"))
      (node (ref "R21") (pin "2") (pinfunction "2_2") (pintype "passive"))
      (node (ref "R22") (pin "2") (pinfunction "2_2") (pintype "passive"))
    )
    (net (code "140") (name "GND") (class "Default")
      (node (ref "C132") (pin "2") (pinfunction "2_2") (pintype "passive"))
      (node (ref "C133") (pin "2") (pinfunction "2_2") (pintype "passive"))
      (node (ref "C134") (pin "2") (pinfunction "2_2") (pintype "passive"))
      (node (ref "C135") (pin "2") (pinfunction "2_2") (pintype "passive"))
      (node (ref "C16") (pin "2") (pinfunction "2_2") (pintype "passive"))
      (node (ref "C25") (pin "2") (pinfunction "2_2") (pintype "passive"))
      (node (ref "C26") (pin "2") (pinfunction "2_2") (pintype "passive"))
      (node (ref "C27") (pin "2") (pinfunction "2_2") (pintype "passive"))
      (node (ref "C28") (pin "2") (pinfunction "2_2") (pintype "passive"))
      (node (ref "C29") (pin "2") (pinfunction "2_2") (pintype "passive"))
      (node (ref "C33") (pin "2") (pinfunction "2_2") (pintype "passive"))
      (node (ref "C34") (pin "2") (pinfunction "2_2") (pintype "passive"))
      (node (ref "C35") (pin "2") (pinfunction "2_2") (pintype "passive"))
      (node (ref "C36") (pin "2") (pinfunction "2_2") (pintype "passive"))
      (node (ref "C37") (pin "2") (pinfunction "2_2") (pintype "passive"))
      (node (ref "C38") (pin "2") (pinfunction "2_2") (pintype "passive"))
      (node (ref "C40") (pin "2") (pinfunction "2_2") (pintype "passive"))
      (node (ref "C41") (pin "2") (pinfunction "2_2") (pintype "passive"))
      (node (ref "C42") (pin "2") (pinfunction "2_2") (pintype "passive"))
      (node (ref "C43") (pin "2") (pinfunction "2_2") (pintype "passive"))
      (node (ref "C45") (pin "2") (pinfunction "2_2") (pintype "passive"))
      (node (ref "C47") (pin "2") (pinfunction "2_2") (pintype "passive"))
      (node (ref "C48") (pin "2") (pinfunction "2_2") (pintype "passive"))
      (node (ref "D6") (pin "2") (pinfunction "ANODE_2") (pintype "passive"))
      (node (ref "J17") (pin "1") (pinfunction "1_1") (pintype "passive"))
      (node (ref "J17") (pin "4") (pinfunction "4_4") (pintype "passive"))
      (node (ref "J2") (pin "10") (pinfunction "10_10") (pintype "passive"))
      (node (ref "J2") (pin "12") (pinfunction "12_12") (pintype "passive"))
      (node (ref "J2") (pin "14") (pinfunction "14_14") (pintype "passive"))
      (node (ref "J2") (pin "16") (pinfunction "16_16") (pintype "passive"))
      (node (ref "J2") (pin "18") (pinfunction "18_18") (pintype "passive"))
      (node (ref "J2") (pin "20") (pinfunction "20_20") (pintype "passive"))
      (node (ref "J2") (pin "4") (pinfunction "4_4") (pintype "passive"))
      (node (ref "J2") (pin "6") (pinfunction "6_6") (pintype "passive"))
      (node (ref "J2") (pin "8") (pinfunction "8_8") (pintype "passive"))
      (node (ref "J20") (pin "1") (pinfunction "1_1") (pintype "passive"))
      (node (ref "J20") (pin "4") (pinfunction "4_4") (pintype "passive"))
      (node (ref "MCU") (pin "106") (pinfunction "GND3_106") (pintype "power_in"))
      (node (ref "MCU") (pin "12") (pinfunction "GND1_12") (pintype "power_in"))
      (node (ref "MCU") (pin "126") (pinfunction "GND4_126") (pintype "power_in"))
      (node (ref "MCU") (pin "33") (pinfunction "GNDPLL_33") (pintype "power_in"))
      (node (ref "MCU") (pin "44") (pinfunction "GNDUTMI_44") (pintype "power_in"))
      (node (ref "MCU") (pin "54") (pinfunction "GNDBU_54") (pintype "power_in"))
      (node (ref "MCU") (pin "58") (pinfunction "GND2_58") (pintype "power_in"))
      (node (ref "MN17") (pin "2") (pinfunction "GND_2") (pintype "power_in"))
      (node (ref "MN18") (pin "2") (pinfunction "GND_2") (pintype "power_in"))
      (node (ref "R131") (pin "1") (pinfunction "1_1") (pintype "passive"))
      (node (ref "R138") (pin "1") (pinfunction "1_1") (pintype "passive"))
      (node (ref "R28") (pin "1") (pinfunction "1_1") (pintype "passive"))
      (node (ref "R29") (pin "1") (pinfunction "1_1") (pintype "passive"))
      (node (ref "Y1") (pin "2") (pinfunction "2_2") (pintype "passive"))
      (node (ref "Y1") (pin "4") (pinfunction "4_4") (pintype "passive"))
    )
    (net (code "141") (name "Net-(D6-CATHODE)") (class "Default")
      (node (ref "C16") (pin "1") (pinfunction "1_1") (pintype "passive"))
      (node (ref "D6") (pin "1") (pinfunction "CATHODE_1") (pintype "passive"))
      (node (ref "JP7") (pin "3") (pinfunction "3_3") (pintype "passive"))
      (node (ref "R27") (pin "1") (pinfunction "1_1") (pintype "passive"))
    )
    (net (code "142") (name "Net-(JP22-Pad2)") (class "Default")
      (node (ref "JP22") (pin "2") (pinfunction "2_2") (pintype "passive"))
      (node (ref "R128") (pin "1") (pinfunction "1_1") (pintype "passive"))
    )
    (net (code "143") (name "Net-(JP23-Pad2)") (class "Default")
      (node (ref "JP23") (pin "2") (pinfunction "2_2") (pintype "passive"))
      (node (ref "R135") (pin "1") (pinfunction "1_1") (pintype "passive"))
    )
    (net (code "144") (name "Net-(MCU-VBG)") (class "Default")
      (node (ref "C48") (pin "1") (pinfunction "1_1") (pintype "passive"))
      (node (ref "MCU") (pin "40") (pinfunction "VBG_40") (pintype "passive"))
      (node (ref "R28") (pin "2") (pinfunction "2_2") (pintype "passive"))
    )
    (net (code "145") (name "Net-(MN17-CANH)") (class "Default")
      (node (ref "J17") (pin "2") (pinfunction "2_2") (pintype "passive"))
      (node (ref "JP22") (pin "1") (pinfunction "1_1") (pintype "passive"))
      (node (ref "MN17") (pin "7") (pinfunction "CANH_7") (pintype "bidirectional"))
    )
    (net (code "146") (name "Net-(MN17-CANL)") (class "Default")
      (node (ref "J17") (pin "3") (pinfunction "3_3") (pintype "passive"))
      (node (ref "MN17") (pin "6") (pinfunction "CANL_6") (pintype "bidirectional"))
      (node (ref "R128") (pin "2") (pinfunction "2_2") (pintype "passive"))
    )
    (net (code "147") (name "Net-(MN17-D)") (class "Default")
      (node (ref "MN17") (pin "1") (pinfunction "D_1") (pintype "input"))
      (node (ref "R127") (pin "2") (pinfunction "2_2") (pintype "passive"))
    )
    (net (code "148") (name "Net-(MN17-EN)") (class "Default")
      (node (ref "MN17") (pin "5") (pinfunction "EN_5") (pintype "input"))
      (node (ref "R129") (pin "1") (pinfunction "1_1") (pintype "passive"))
    )
    (net (code "149") (name "Net-(MN17-R)") (class "Default")
      (node (ref "MN17") (pin "4") (pinfunction "R_4") (pintype "output"))
      (node (ref "R130") (pin "2") (pinfunction "2_2") (pintype "passive"))
    )
    (net (code "150") (name "Net-(MN17-RS)") (class "Default")
      (node (ref "MN17") (pin "8") (pinfunction "RS_8") (pintype "input"))
      (node (ref "R126") (pin "2") (pinfunction "2_2") (pintype "passive"))
      (node (ref "R131") (pin "2") (pinfunction "2_2") (pintype "passive"))
    )
    (net (code "151") (name "Net-(MN18-CANH)") (class "Default")
      (node (ref "J20") (pin "2") (pinfunction "2_2") (pintype "passive"))
      (node (ref "JP23") (pin "1") (pinfunction "1_1") (pintype "passive"))
      (node (ref "MN18") (pin "7") (pinfunction "CANH_7") (pintype "bidirectional"))
    )
    (net (code "152") (name "Net-(MN18-CANL)") (class "Default")
      (node (ref "J20") (pin "3") (pinfunction "3_3") (pintype "passive"))
      (node (ref "MN18") (pin "6") (pinfunction "CANL_6") (pintype "bidirectional"))
      (node (ref "R135") (pin "2") (pinfunction "2_2") (pintype "passive"))
    )
    (net (code "153") (name "Net-(MN18-D)") (class "Default")
      (node (ref "MN18") (pin "1") (pinfunction "D_1") (pintype "input"))
      (node (ref "R133") (pin "2") (pinfunction "2_2") (pintype "passive"))
    )
    (net (code "154") (name "Net-(MN18-EN)") (class "Default")
      (node (ref "MN18") (pin "5") (pinfunction "EN_5") (pintype "input"))
      (node (ref "R136") (pin "1") (pinfunction "1_1") (pintype "passive"))
    )
    (net (code "155") (name "Net-(MN18-R)") (class "Default")
      (node (ref "MN18") (pin "4") (pinfunction "R_4") (pintype "output"))
      (node (ref "R137") (pin "2") (pinfunction "2_2") (pintype "passive"))
    )
    (net (code "156") (name "Net-(MN18-RS)") (class "Default")
      (node (ref "MN18") (pin "8") (pinfunction "RS_8") (pintype "input"))
      (node (ref "R134") (pin "2") (pinfunction "2_2") (pintype "passive"))
      (node (ref "R138") (pin "2") (pinfunction "2_2") (pintype "passive"))
    )
    (net (code "157") (name "unconnected-(D6-NC-Pad3)") (class "Default")
      (node (ref "D6") (pin "3") (pinfunction "NC_3") (pintype "passive+no_connect"))
    )
  )
)
